# sema_1.net
KiCad netlist of a schematic drawn in Altium Designer
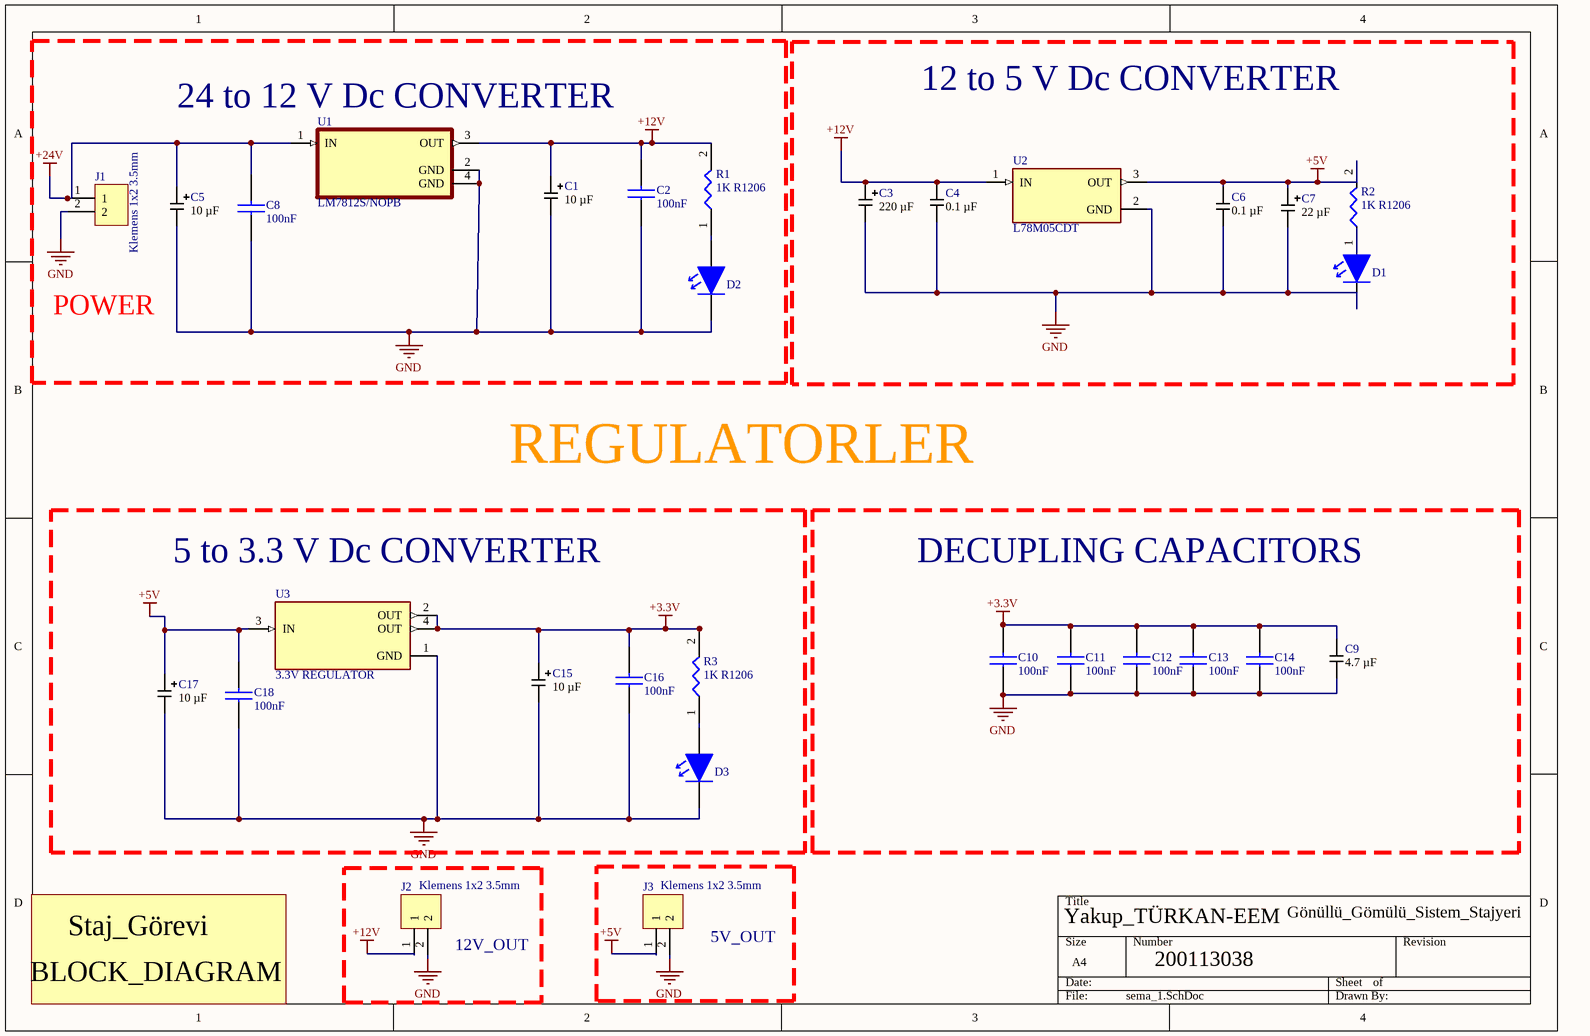
[diagram p0: sema_1.SchDoc]

(export (version "E")
  (design (tool "Eeschema 10.0.6"))
  (components
    (comp (ref "C1")
      (value "10uF")
      (footprint "KEMET_CAP_TAN-B")
      (description "CAP TANT 10UF 20% 16V 1411")
      (fields (field (name "CAPACITANCE") "10 µF"))
      (libsource (lib "HAMLE") (part "10uF"))
    )
    (comp (ref "C2")
      (value "C0603C104K5RACTU")
      (footprint "CAP_0603")
      (description "CAP CER 100nF %10 0603 SMD")
      (fields
        (field (name "MANUFACTURER") "KEMET")
        (field (name "TOLERANCE") "10%")
        (field (name "CAPACITANCE") "100nF")
        (field (name "DESIGNED BY") "BERK")
      )
      (libsource (lib "HAMLE") (part "CAP CER 100nF 0603"))
    )
    (comp (ref "C3")
      (value "220uF")
      (footprint "KYOCERA_CAP_TAN-C")
      (description "CAP TANT 220UF 20% 10V 2312")
      (fields (field (name "CAPACITANCE") "220 µF"))
      (libsource (lib "HAMLE") (part "220uF"))
    )
    (comp (ref "C4")
      (value "0.1uF")
      (footprint "SAMSUNG_CAP_0805_095")
      (description "CAP CER 0.1UF 25V X7R 0805")
      (fields (field (name "CAPACITANCE") "0.1 µF"))
      (libsource (lib "HAMLE") (part "0.1uF"))
    )
    (comp (ref "C5")
      (value "10uF")
      (footprint "KEMET_CAP_TAN-B")
      (description "CAP TANT 10UF 20% 16V 1411")
      (fields (field (name "CAPACITANCE") "10 µF"))
      (libsource (lib "HAMLE") (part "10uF"))
    )
    (comp (ref "C6")
      (value "0.1uF")
      (footprint "SAMSUNG_CAP_0805_095")
      (description "CAP CER 0.1UF 25V X7R 0805")
      (fields (field (name "CAPACITANCE") "0.1 µF"))
      (libsource (lib "HAMLE") (part "0.1uF"))
    )
    (comp (ref "C7")
      (value "22uF")
      (footprint "KEMET_CAP_TAN-B")
      (description "CAP TANT 22UF 10% 20V 1411")
      (fields (field (name "CAPACITANCE") "22 µF"))
      (libsource (lib "HAMLE") (part "22uF"))
    )
    (comp (ref "C8")
      (value "C0603C104K5RACTU")
      (footprint "CAP_0603")
      (description "CAP CER 100nF %10 0603 SMD")
      (fields
        (field (name "MANUFACTURER") "KEMET")
        (field (name "TOLERANCE") "10%")
        (field (name "CAPACITANCE") "100nF")
        (field (name "DESIGNED BY") "BERK")
      )
      (libsource (lib "HAMLE") (part "CAP CER 100nF 0603"))
    )
    (comp (ref "C9")
      (value "4.7uF")
      (footprint "SAMSUNG_CAP_0805_095")
      (description "CAP CER 4.7UF 25V X5R 0805")
      (fields (field (name "CAPACITANCE") "4.7 µF"))
      (libsource (lib "HAMLE") (part "4.7uF"))
    )
    (comp (ref "C10")
      (value "C0603C104K5RACTU")
      (footprint "CAP_0603")
      (description "CAP CER 100nF %10 0603 SMD")
      (fields
        (field (name "MANUFACTURER") "KEMET")
        (field (name "TOLERANCE") "10%")
        (field (name "CAPACITANCE") "100nF")
        (field (name "DESIGNED BY") "BERK")
      )
      (libsource (lib "HAMLE") (part "CAP CER 100nF 0603"))
    )
    (comp (ref "C11")
      (value "C0603C104K5RACTU")
      (footprint "CAP_0603")
      (description "CAP CER 100nF %10 0603 SMD")
      (fields
        (field (name "MANUFACTURER") "KEMET")
        (field (name "TOLERANCE") "10%")
        (field (name "CAPACITANCE") "100nF")
        (field (name "DESIGNED BY") "BERK")
      )
      (libsource (lib "HAMLE") (part "CAP CER 100nF 0603"))
    )
    (comp (ref "C12")
      (value "C0603C104K5RACTU")
      (footprint "CAP_0603")
      (description "CAP CER 100nF %10 0603 SMD")
      (fields
        (field (name "MANUFACTURER") "KEMET")
        (field (name "TOLERANCE") "10%")
        (field (name "CAPACITANCE") "100nF")
        (field (name "DESIGNED BY") "BERK")
      )
      (libsource (lib "HAMLE") (part "CAP CER 100nF 0603"))
    )
    (comp (ref "C13")
      (value "C0603C104K5RACTU")
      (footprint "CAP_0603")
      (description "CAP CER 100nF %10 0603 SMD")
      (fields
        (field (name "MANUFACTURER") "KEMET")
        (field (name "TOLERANCE") "10%")
        (field (name "CAPACITANCE") "100nF")
        (field (name "DESIGNED BY") "BERK")
      )
      (libsource (lib "HAMLE") (part "CAP CER 100nF 0603"))
    )
    (comp (ref "C14")
      (value "C0603C104K5RACTU")
      (footprint "CAP_0603")
      (description "CAP CER 100nF %10 0603 SMD")
      (fields
        (field (name "MANUFACTURER") "KEMET")
        (field (name "TOLERANCE") "10%")
        (field (name "CAPACITANCE") "100nF")
        (field (name "DESIGNED BY") "BERK")
      )
      (libsource (lib "HAMLE") (part "CAP CER 100nF 0603"))
    )
    (comp (ref "C15")
      (value "10uF")
      (footprint "KEMET_CAP_TAN-B")
      (description "CAP TANT 10UF 20% 16V 1411")
      (fields (field (name "CAPACITANCE") "10 µF"))
      (libsource (lib "HAMLE") (part "10uF"))
    )
    (comp (ref "C16")
      (value "C0603C104K5RACTU")
      (footprint "CAP_0603")
      (description "CAP CER 100nF %10 0603 SMD")
      (fields
        (field (name "MANUFACTURER") "KEMET")
        (field (name "TOLERANCE") "10%")
        (field (name "CAPACITANCE") "100nF")
        (field (name "DESIGNED BY") "BERK")
      )
      (libsource (lib "HAMLE") (part "CAP CER 100nF 0603"))
    )
    (comp (ref "C17")
      (value "10uF")
      (footprint "KEMET_CAP_TAN-B")
      (description "CAP TANT 10UF 20% 16V 1411")
      (fields (field (name "CAPACITANCE") "10 µF"))
      (libsource (lib "HAMLE") (part "10uF"))
    )
    (comp (ref "C18")
      (value "C0603C104K5RACTU")
      (footprint "CAP_0603")
      (description "CAP CER 100nF %10 0603 SMD")
      (fields
        (field (name "MANUFACTURER") "KEMET")
        (field (name "TOLERANCE") "10%")
        (field (name "CAPACITANCE") "100nF")
        (field (name "DESIGNED BY") "BERK")
      )
      (libsource (lib "HAMLE") (part "CAP CER 100nF 0603"))
    )
    (comp (ref "D1")
      (value "LH R974-LP-1")
      (footprint "LED_RED_0805")
      (description "LED Uni-Color Hyper Red 660nm 2-Pin Chip 0805(2012Metric) T/R")
      (fields (field (name "MANUFACTURER") "Osram Opto") (field (name "DESIGNED BY") "BERK"))
      (libsource (lib "HAMLE") (part "LED RED 0805"))
    )
    (comp (ref "D2")
      (value "LH R974-LP-1")
      (footprint "LED_RED_0805")
      (description "LED Uni-Color Hyper Red 660nm 2-Pin Chip 0805(2012Metric) T/R")
      (fields (field (name "MANUFACTURER") "Osram Opto") (field (name "DESIGNED BY") "BERK"))
      (libsource (lib "HAMLE") (part "LED RED 0805"))
    )
    (comp (ref "D3")
      (value "LTST-C171GKT")
      (footprint "LED_GREEN_0805")
      (description "Green 0805 130 º Min 5 mcd Typical 12 mcd Water Clear Lens SMT LED")
      (fields (field (name "MANUFACTURER") "Vishay Lite-On") (field (name "DESIGNED BY") "BERK"))
      (libsource (lib "HAMLE") (part "LED GREEN 0805"))
    )
    (comp (ref "J1")
      (value "Klemens 1x2 3.5mm")
      (footprint "Klemens 1x2 - 3.5mm")
      (libsource (lib "HAMLE") (part "Klemens 1x2 3.5mm"))
    )
    (comp (ref "J2")
      (value "Klemens 1x2 3.5mm")
      (footprint "Klemens 1x2 - 3.5mm")
      (libsource (lib "ilk") (part "Klemens 1x2 3.5mm"))
    )
    (comp (ref "J3")
      (value "Klemens 1x2 3.5mm")
      (footprint "Klemens 1x2 - 3.5mm")
      (libsource (lib "ilk") (part "Klemens 1x2 3.5mm"))
    )
    (comp (ref "R1")
      (value "1K R1206")
      (footprint "R1206 Resıstor")
      (libsource (lib "HAMLE") (part "1K R1206"))
    )
    (comp (ref "R2")
      (value "1K R1206")
      (footprint "R1206 Resıstor")
      (libsource (lib "HAMLE") (part "1K R1206"))
    )
    (comp (ref "R3")
      (value "1K R1206")
      (footprint "R1206 Resıstor")
      (libsource (lib "HAMLE") (part "1K R1206"))
    )
    (comp (ref "U1")
      (value "LM7812S/NOPB")
      (footprint "LM7812S_NOPB:TO254P1524X483-4N")
      (fields (field (name "MF") "{'manufacturer': u'Texas Instruments'}"))
      (libsource (lib "HAMLE") (part "LM7812S/NOPB"))
    )
    (comp (ref "U2")
      (value "L78M05CDT")
      (footprint "L78M05CDT:VREG_L78M05CDT")
      (description "Linear Voltage Regulator IC 1 Output 500mA DPAK")
      (fields (field (name "MF") "{'manufacturer': u'STMicroelectronics'}"))
      (libsource (lib "HAMLE") (part "L78M05CDT"))
    )
    (comp (ref "U3")
      (value "3.3V REGULATOR")
      (footprint "LD1117S33TR:SOT230P700X180-4N")
      (description "LDO Voltage Regulators 3.3V 0.8A Positive")
      (fields (field (name "MP") "LD1117S33TR") (field (name "MF") "{'manufacturer': u'STMicroelectronics'}"))
      (libsource (lib "HAMLE") (part "3.3V REGULATOR"))
    )
  )
  (nets
    (net (code "1") (name "+3.3V") (class "Default")
      (node (ref "C10") (pin "2") (pinfunction "2_2") (pintype "passive"))
      (node (ref "C11") (pin "2") (pinfunction "2_2") (pintype "passive"))
      (node (ref "C12") (pin "2") (pinfunction "2_2") (pintype "passive"))
      (node (ref "C13") (pin "2") (pinfunction "2_2") (pintype "passive"))
      (node (ref "C14") (pin "2") (pinfunction "2_2") (pintype "passive"))
      (node (ref "C15") (pin "1") (pinfunction "1_1") (pintype "passive"))
      (node (ref "C16") (pin "2") (pinfunction "2_2") (pintype "passive"))
      (node (ref "C9") (pin "2") (pinfunction "2_2") (pintype "passive"))
      (node (ref "R3") (pin "2") (pinfunction "2_2") (pintype "passive"))
      (node (ref "U3") (pin "2") (pinfunction "OUT_2") (pintype "output"))
      (node (ref "U3") (pin "4") (pinfunction "OUT_4") (pintype "output"))
    )
    (net (code "2") (name "+5V") (class "Default")
      (node (ref "C17") (pin "1") (pinfunction "1_1") (pintype "passive"))
      (node (ref "C18") (pin "2") (pinfunction "2_2") (pintype "passive"))
      (node (ref "C6") (pin "2") (pinfunction "2_2") (pintype "passive"))
      (node (ref "C7") (pin "1") (pinfunction "1_1") (pintype "passive"))
      (node (ref "J3") (pin "1") (pinfunction "1_1") (pintype "passive"))
      (node (ref "R2") (pin "2") (pinfunction "2_2") (pintype "passive"))
      (node (ref "U2") (pin "3") (pinfunction "OUT_3") (pintype "output"))
      (node (ref "U3") (pin "3") (pinfunction "IN_3") (pintype "input"))
    )
    (net (code "3") (name "+12V") (class "Default")
      (node (ref "C1") (pin "1") (pinfunction "1_1") (pintype "passive"))
      (node (ref "C2") (pin "2") (pinfunction "2_2") (pintype "passive"))
      (node (ref "C3") (pin "1") (pinfunction "1_1") (pintype "passive"))
      (node (ref "C4") (pin "2") (pinfunction "2_2") (pintype "passive"))
      (node (ref "J2") (pin "1") (pinfunction "1_1") (pintype "passive"))
      (node (ref "R1") (pin "2") (pinfunction "2_2") (pintype "passive"))
      (node (ref "U1") (pin "3") (pinfunction "OUT_3") (pintype "output"))
      (node (ref "U2") (pin "1") (pinfunction "IN_1") (pintype "input"))
    )
    (net (code "4") (name "+24V") (class "Default")
      (node (ref "C5") (pin "1") (pinfunction "1_1") (pintype "passive"))
      (node (ref "C8") (pin "2") (pinfunction "2_2") (pintype "passive"))
      (node (ref "J1") (pin "1") (pinfunction "1_1") (pintype "passive"))
      (node (ref "U1") (pin "1") (pinfunction "IN_1") (pintype "input"))
    )
    (net (code "5") (name "GND") (class "Default")
      (node (ref "C1") (pin "2") (pinfunction "2_2") (pintype "passive"))
      (node (ref "C10") (pin "1") (pinfunction "1_1") (pintype "passive"))
      (node (ref "C11") (pin "1") (pinfunction "1_1") (pintype "passive"))
      (node (ref "C12") (pin "1") (pinfunction "1_1") (pintype "passive"))
      (node (ref "C13") (pin "1") (pinfunction "1_1") (pintype "passive"))
      (node (ref "C14") (pin "1") (pinfunction "1_1") (pintype "passive"))
      (node (ref "C15") (pin "2") (pinfunction "2_2") (pintype "passive"))
      (node (ref "C16") (pin "1") (pinfunction "1_1") (pintype "passive"))
      (node (ref "C17") (pin "2") (pinfunction "2_2") (pintype "passive"))
      (node (ref "C18") (pin "1") (pinfunction "1_1") (pintype "passive"))
      (node (ref "C2") (pin "1") (pinfunction "1_1") (pintype "passive"))
      (node (ref "C3") (pin "2") (pinfunction "2_2") (pintype "passive"))
      (node (ref "C4") (pin "1") (pinfunction "1_1") (pintype "passive"))
      (node (ref "C5") (pin "2") (pinfunction "2_2") (pintype "passive"))
      (node (ref "C6") (pin "1") (pinfunction "1_1") (pintype "passive"))
      (node (ref "C7") (pin "2") (pinfunction "2_2") (pintype "passive"))
      (node (ref "C8") (pin "1") (pinfunction "1_1") (pintype "passive"))
      (node (ref "C9") (pin "1") (pinfunction "1_1") (pintype "passive"))
      (node (ref "D1") (pin "1") (pinfunction "1_1") (pintype "power_in"))
      (node (ref "D2") (pin "1") (pinfunction "1_1") (pintype "power_in"))
      (node (ref "D3") (pin "1") (pinfunction "1_1") (pintype "power_in"))
      (node (ref "J1") (pin "2") (pinfunction "2_2") (pintype "passive"))
      (node (ref "J2") (pin "2") (pinfunction "2_2") (pintype "passive"))
      (node (ref "J3") (pin "2") (pinfunction "2_2") (pintype "passive"))
      (node (ref "U1") (pin "2") (pinfunction "GND_2") (pintype "power_in"))
      (node (ref "U1") (pin "4") (pinfunction "GND_4") (pintype "power_in"))
      (node (ref "U2") (pin "2") (pinfunction "GND_2") (pintype "power_in"))
      (node (ref "U3") (pin "1") (pinfunction "GND_1") (pintype "power_in"))
    )
    (net (code "6") (name "Net-(D1-Pad2)") (class "Default")
      (node (ref "D1") (pin "2") (pinfunction "2_2") (pintype "power_in"))
      (node (ref "R2") (pin "1") (pinfunction "1_1") (pintype "passive"))
    )
    (net (code "7") (name "Net-(D2-Pad2)") (class "Default")
      (node (ref "D2") (pin "2") (pinfunction "2_2") (pintype "power_in"))
      (node (ref "R1") (pin "1") (pinfunction "1_1") (pintype "passive"))
    )
    (net (code "8") (name "Net-(D3-Pad2)") (class "Default")
      (node (ref "D3") (pin "2") (pinfunction "2_2") (pintype "power_in"))
      (node (ref "R3") (pin "1") (pinfunction "1_1") (pintype "passive"))
    )
  )
)
